# Mcu.net
KiCad netlist of a schematic drawn in Altium Designer
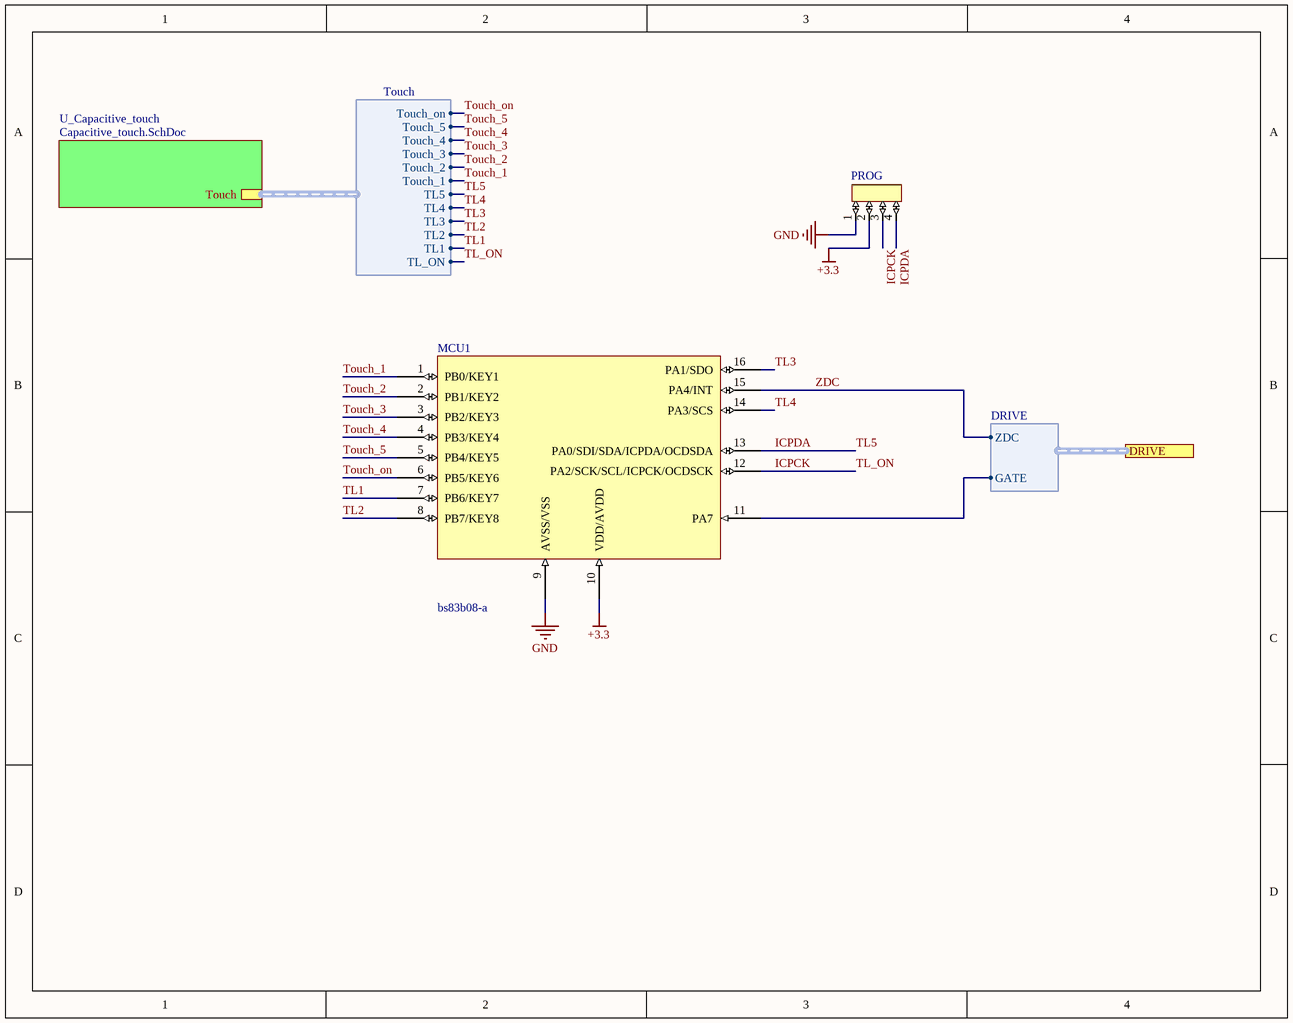
[diagram p0: Mcu.SchDoc]

(export (version "E")
  (design (tool "Eeschema 10.0.6"))
  (components
    (comp (ref "MCU1")
      (value "bs83b08-a")
      (footprint "bs83b08-a")
      (libsource (lib "kave-eng-pro") (part "bs83b08-a"))
    )
    (comp (ref "PROG")
      (value "~")
      (footprint "CONECTOR/XH/4PIN")
      (libsource (lib "kave-eng-pro") (part "CONECTOR/XH/4PIN"))
    )
  )
  (nets
    (net (code "3") (name "+3.3") (class "Default")
      (node (ref "MCU1") (pin "10") (pinfunction "VDD/AVDD_10") (pintype "input"))
      (node (ref "PROG") (pin "2") (pintype "bidirectional"))
    )
    (net (code "4") (name "/GATE") (class "Default")
      (node (ref "MCU1") (pin "11") (pinfunction "PA7_11") (pintype "input"))
    )
    (net (code "5") (name "/ICPCK") (class "Default")
      (node (ref "MCU1") (pin "12") (pinfunction "PA2/SCK/SCL/ICPCK/OCDSCK_12") (pintype "bidirectional"))
      (node (ref "PROG") (pin "3") (pintype "bidirectional"))
    )
    (net (code "6") (name "/ICPDA") (class "Default")
      (node (ref "MCU1") (pin "13") (pinfunction "PA0/SDI/SDA/ICPDA/OCDSDA_13") (pintype "bidirectional"))
      (node (ref "PROG") (pin "4") (pintype "bidirectional"))
    )
    (net (code "7") (name "/TL1") (class "Default")
      (node (ref "MCU1") (pin "7") (pinfunction "PB6/KEY7_7") (pintype "bidirectional"))
    )
    (net (code "8") (name "/TL2") (class "Default")
      (node (ref "MCU1") (pin "8") (pinfunction "PB7/KEY8_8") (pintype "bidirectional"))
    )
    (net (code "9") (name "/TL3") (class "Default")
      (node (ref "MCU1") (pin "16") (pinfunction "PA1/SDO_16") (pintype "bidirectional"))
    )
    (net (code "10") (name "/TL4") (class "Default")
      (node (ref "MCU1") (pin "14") (pinfunction "PA3/SCS_14") (pintype "bidirectional"))
    )
    (net (code "11") (name "/Touch_1") (class "Default")
      (node (ref "MCU1") (pin "1") (pinfunction "PB0/KEY1_1") (pintype "bidirectional"))
    )
    (net (code "12") (name "/Touch_2") (class "Default")
      (node (ref "MCU1") (pin "2") (pinfunction "PB1/KEY2_2") (pintype "bidirectional"))
    )
    (net (code "13") (name "/Touch_3") (class "Default")
      (node (ref "MCU1") (pin "3") (pinfunction "PB2/KEY3_3") (pintype "bidirectional"))
    )
    (net (code "14") (name "/Touch_4") (class "Default")
      (node (ref "MCU1") (pin "4") (pinfunction "PB3/KEY4_4") (pintype "bidirectional"))
    )
    (net (code "15") (name "/Touch_5") (class "Default")
      (node (ref "MCU1") (pin "5") (pinfunction "PB4/KEY5_5") (pintype "bidirectional"))
    )
    (net (code "16") (name "/Touch_on") (class "Default")
      (node (ref "MCU1") (pin "6") (pinfunction "PB5/KEY6_6") (pintype "bidirectional"))
    )
    (net (code "17") (name "/ZDC") (class "Default")
      (node (ref "MCU1") (pin "15") (pinfunction "PA4/INT_15") (pintype "bidirectional"))
    )
    (net (code "20") (name "GND") (class "Default")
      (node (ref "MCU1") (pin "9") (pinfunction "AVSS/VSS_9") (pintype "input"))
      (node (ref "PROG") (pin "1") (pintype "bidirectional"))
    )
  )
)
